# Output.net
KiCad netlist of a schematic drawn in Altium Designer
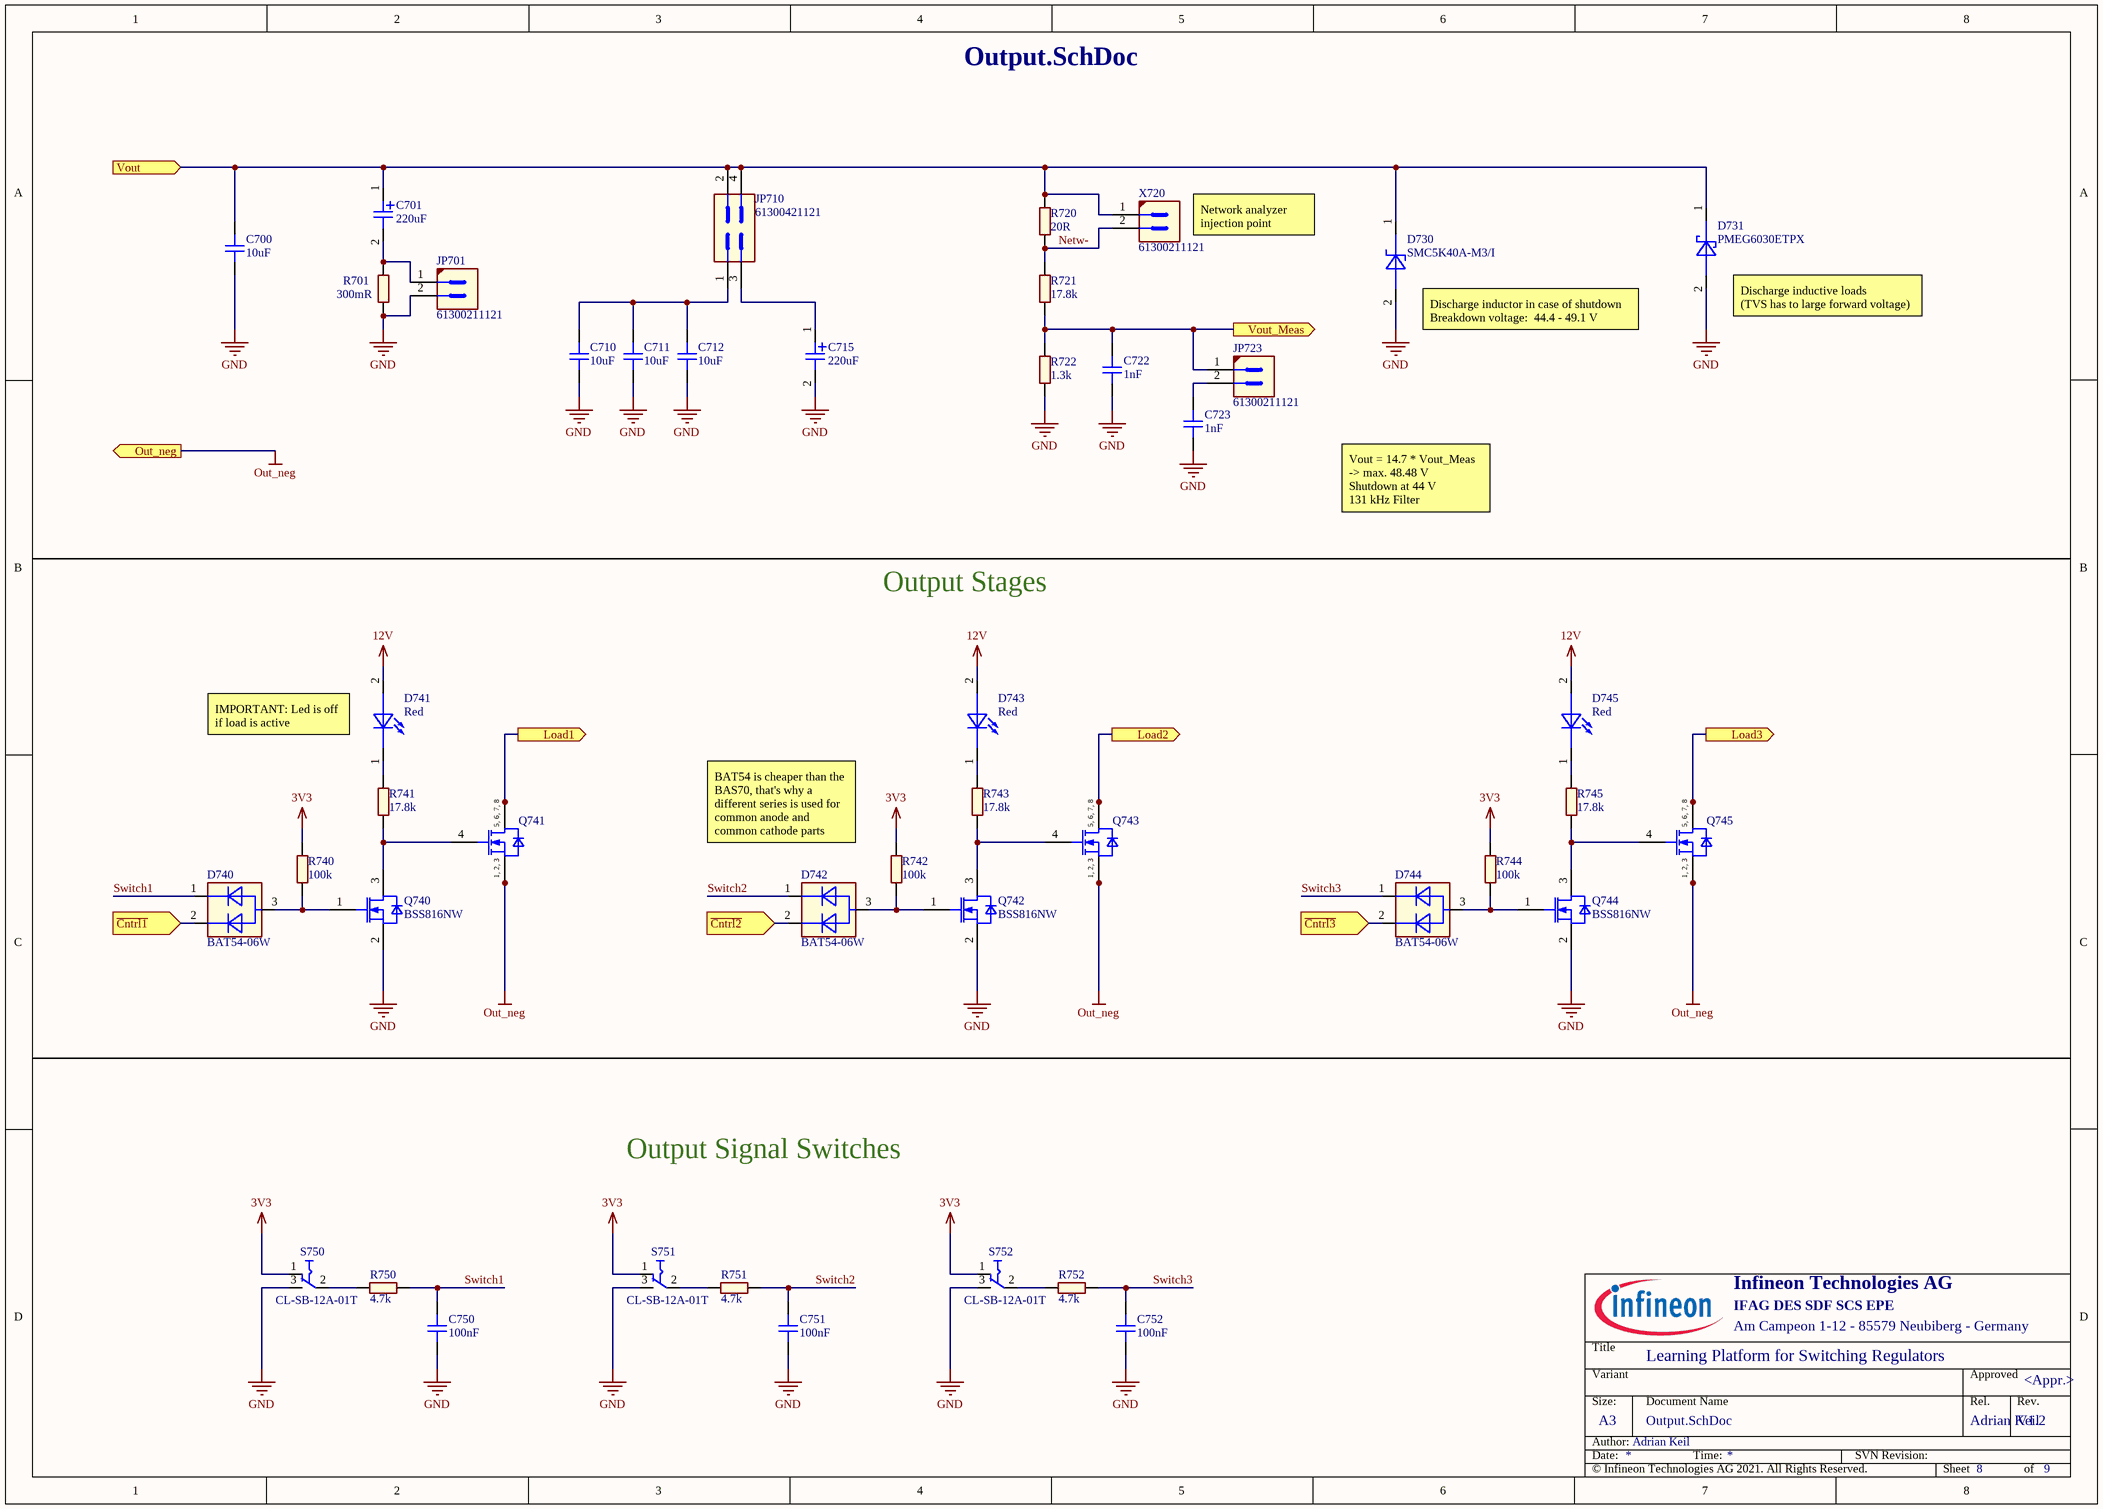
[diagram p0: Output.SchDoc]

(export (version "E")
  (design (tool "Eeschema 10.0.6"))
  (components
    (comp (ref "C700")
      (value "10uF")
      (footprint "CAPC3216X190N-1")
      (description "CAP / CERA / 10uF / 50V / 20% / X5R (EIA) / -55°C to 85°C / 1206 (3216) / SMD / -")
      (fields (field (name "MANUFACTURER") "Taiyo Yuden"))
      (libsource (lib "PCBLibraryData") (part "CAP-SGL-STD-02P_00000001"))
    )
    (comp (ref "C701")
      (value "220uF")
      (footprint "CAPAE1030X1050N-2")
      (fields (field (name "MANUFACTURER") "Wurth Elektronik"))
      (libsource (lib "PCBLibraryData") (part "CAP-SGL-POL-02P_00000002"))
    )
    (comp (ref "C710")
      (value "10uF")
      (footprint "CAPC3216X190N-1")
      (description "CAP / CERA / 10uF / 50V / 20% / X5R (EIA) / -55°C to 85°C / 1206 (3216) / SMD / -")
      (fields (field (name "MANUFACTURER") "Taiyo Yuden"))
      (libsource (lib "PCBLibraryData") (part "CAP-SGL-STD-02P_00000001"))
    )
    (comp (ref "C711")
      (value "10uF")
      (footprint "CAPC3216X190N-1")
      (description "CAP / CERA / 10uF / 50V / 20% / X5R (EIA) / -55°C to 85°C / 1206 (3216) / SMD / -")
      (fields (field (name "MANUFACTURER") "Taiyo Yuden"))
      (libsource (lib "PCBLibraryData") (part "CAP-SGL-STD-02P_00000001"))
    )
    (comp (ref "C712")
      (value "10uF")
      (footprint "CAPC3216X190N-1")
      (description "CAP / CERA / 10uF / 50V / 20% / X5R (EIA) / -55°C to 85°C / 1206 (3216) / SMD / -")
      (fields (field (name "MANUFACTURER") "Taiyo Yuden"))
      (libsource (lib "PCBLibraryData") (part "CAP-SGL-STD-02P_00000001"))
    )
    (comp (ref "C715")
      (value "220uF")
      (footprint "CAPAE1030X1050N-2")
      (fields (field (name "MANUFACTURER") "Wurth Elektronik"))
      (libsource (lib "PCBLibraryData") (part "CAP-SGL-POL-02P_00000002"))
    )
    (comp (ref "C722")
      (value "1nF")
      (footprint "CAPC1608X87N-1")
      (description "CAP / CERA / 1nF / 50V / 10% / X7R (EIA) / -55°C to 125°C / 0603 (1608) / SMD / -")
      (fields (field (name "MANUFACTURER") "Wurth Elektronik"))
      (libsource (lib "PCBLibraryData") (part "CAP-SGL-STD-02P_00000001"))
    )
    (comp (ref "C723")
      (value "1nF")
      (footprint "CAPC1608X87N-1")
      (description "CAP / CERA / 1nF / 50V / 10% / X7R (EIA) / -55°C to 125°C / 0603 (1608) / SMD / -")
      (fields (field (name "MANUFACTURER") "Wurth Elektronik"))
      (libsource (lib "PCBLibraryData") (part "CAP-SGL-STD-02P_00000001"))
    )
    (comp (ref "C750")
      (value "100nF")
      (footprint "CAPC1608X90N-2")
      (description "CAP / CERA / 100nF / 50V / 10% / X7R (EIA) / -55°C to 125°C / 0603 / SMD / -")
      (fields (field (name "MANUFACTURER") "AVX"))
      (libsource (lib "PCBLibraryData") (part "CAP-SGL-STD-02P_00000001"))
    )
    (comp (ref "C751")
      (value "100nF")
      (footprint "CAPC1608X90N-2")
      (description "CAP / CERA / 100nF / 50V / 10% / X7R (EIA) / -55°C to 125°C / 0603 / SMD / -")
      (fields (field (name "MANUFACTURER") "AVX"))
      (libsource (lib "PCBLibraryData") (part "CAP-SGL-STD-02P_00000001"))
    )
    (comp (ref "C752")
      (value "100nF")
      (footprint "CAPC1608X90N-2")
      (description "CAP / CERA / 100nF / 50V / 10% / X7R (EIA) / -55°C to 125°C / 0603 / SMD / -")
      (fields (field (name "MANUFACTURER") "AVX"))
      (libsource (lib "PCBLibraryData") (part "CAP-SGL-STD-02P_00000001"))
    )
    (comp (ref "D730")
      (value "SMC5K40A-M3/I")
      (footprint "DIOM7959X262N")
      (description "Surface Mount Transient Voltage Suppressors, Unidirectional, Very Fast Response Time")
      (fields (field (name "MANUFACTURER") "Vishay"))
      (libsource (lib "PCBLibraryData") (part "d_tvs_a"))
    )
    (comp (ref "D731")
      (value "PMEG6030ETPX")
      (footprint "SODFL4725X110N")
      (description "DIODE SCHOTTKY 60V 3A SOD128")
      (fields (field (name "MANUFACTURER") "Nexperia"))
      (libsource (lib "PCBLibraryData") (part "d_schottky_a"))
    )
    (comp (ref "D740")
      (value "BAT54-06W")
      (footprint "SOT65P210X100-3N-1-V")
      (description "Silicon Schottky Diodes")
      (fields (field (name "MANUFACTURER") "Infineon Technologies"))
      (libsource (lib "PCBLibraryData") (part "d_dual_c1c2a3_3p"))
    )
    (comp (ref "D741")
      (value "Red")
      (footprint "LEDSC160X80X80-2N-1")
      (description "WL-SMCW SMT Mono-color Chip LED Waterclear, Red,630nm")
      (fields (field (name "MANUFACTURER") "Wurth Elektronik"))
      (libsource (lib "PCBLibraryData") (part "d_led_a"))
    )
    (comp (ref "D742")
      (value "BAT54-06W")
      (footprint "SOT65P210X100-3N-1-V")
      (description "Silicon Schottky Diodes")
      (fields (field (name "MANUFACTURER") "Infineon Technologies"))
      (libsource (lib "PCBLibraryData") (part "d_dual_c1c2a3_3p"))
    )
    (comp (ref "D743")
      (value "Red")
      (footprint "LEDSC160X80X80-2N-1")
      (description "WL-SMCW SMT Mono-color Chip LED Waterclear, Red,630nm")
      (fields (field (name "MANUFACTURER") "Wurth Elektronik"))
      (libsource (lib "PCBLibraryData") (part "d_led_a"))
    )
    (comp (ref "D744")
      (value "BAT54-06W")
      (footprint "SOT65P210X100-3N-1-V")
      (description "Silicon Schottky Diodes")
      (fields (field (name "MANUFACTURER") "Infineon Technologies"))
      (libsource (lib "PCBLibraryData") (part "d_dual_c1c2a3_3p"))
    )
    (comp (ref "D745")
      (value "Red")
      (footprint "LEDSC160X80X80-2N-1")
      (description "WL-SMCW SMT Mono-color Chip LED Waterclear, Red,630nm")
      (fields (field (name "MANUFACTURER") "Wurth Elektronik"))
      (libsource (lib "PCBLibraryData") (part "d_led_a"))
    )
    (comp (ref "JP701")
      (value "61300211121")
      (footprint "CON-M-THT-61300211121")
      (description "Header, 2.54mm Pitch, 2 pin, Vertical, Single Row")
      (fields
        (field (name "LEGACY PARTNUMBER") "CON01500943")
        (field (name "MANUFACTURER") "Wurth Elektronik")
      )
      (libsource (lib "PCBLibraryData") (part "Header 2"))
    )
    (comp (ref "JP710")
      (value "61300421121")
      (footprint "CON-M-THT-61300421121")
      (description "Header, 4pins, 2.54mm pitch, Board to Board")
      (fields (field (name "MANUFACTURER") "Wurth Elektronik"))
      (libsource (lib "PCBLibraryData") (part "Header 2X2"))
    )
    (comp (ref "JP723")
      (value "61300211121")
      (footprint "CON-M-THT-61300211121")
      (description "Header, 2.54mm Pitch, 2 pin, Vertical, Single Row")
      (fields
        (field (name "LEGACY PARTNUMBER") "CON01500943")
        (field (name "MANUFACTURER") "Wurth Elektronik")
      )
      (libsource (lib "PCBLibraryData") (part "Header 2"))
    )
    (comp (ref "Q740")
      (value "BSS816NW")
      (footprint "SOT65P210X100-3N-1-V")
      (description "OptiMOS 2 Small-Signal-Transistor")
      (fields (field (name "MANUFACTURER") "Infineon Technologies"))
      (libsource (lib "PCBLibraryData") (part "igfet_n_ch_dep_dio_1g2s3d_3p"))
    )
    (comp (ref "Q741")
      (value "igfet_n_ch_enh_dio_1s2s3s4g5d6d7d8d_8p")
      (footprint "INF-PG-TSDSON-8-FL")
      (description "OptiMOS Power - MOSFET, 60 V")
      (fields
        (field (name "LEGACY PARTNUMBER") "IFX01400359")
        (field (name "MANUFACTURER") "Infineon Technologies")
      )
      (libsource (lib "PCBLibraryData") (part "igfet_n_ch_enh_dio_1s2s3s4g5d6d7d8d_8p"))
    )
    (comp (ref "Q742")
      (value "BSS816NW")
      (footprint "SOT65P210X100-3N-1-V")
      (description "OptiMOS 2 Small-Signal-Transistor")
      (fields (field (name "MANUFACTURER") "Infineon Technologies"))
      (libsource (lib "PCBLibraryData") (part "igfet_n_ch_dep_dio_1g2s3d_3p"))
    )
    (comp (ref "Q743")
      (value "igfet_n_ch_enh_dio_1s2s3s4g5d6d7d8d_8p")
      (footprint "INF-PG-TSDSON-8-FL")
      (description "OptiMOS Power - MOSFET, 60 V")
      (fields
        (field (name "LEGACY PARTNUMBER") "IFX01400359")
        (field (name "MANUFACTURER") "Infineon Technologies")
      )
      (libsource (lib "PCBLibraryData") (part "igfet_n_ch_enh_dio_1s2s3s4g5d6d7d8d_8p"))
    )
    (comp (ref "Q744")
      (value "BSS816NW")
      (footprint "SOT65P210X100-3N-1-V")
      (description "OptiMOS 2 Small-Signal-Transistor")
      (fields (field (name "MANUFACTURER") "Infineon Technologies"))
      (libsource (lib "PCBLibraryData") (part "igfet_n_ch_dep_dio_1g2s3d_3p"))
    )
    (comp (ref "Q745")
      (value "igfet_n_ch_enh_dio_1s2s3s4g5d6d7d8d_8p")
      (footprint "INF-PG-TSDSON-8-FL")
      (description "OptiMOS Power - MOSFET, 60 V")
      (fields
        (field (name "LEGACY PARTNUMBER") "IFX01400359")
        (field (name "MANUFACTURER") "Infineon Technologies")
      )
      (libsource (lib "PCBLibraryData") (part "igfet_n_ch_enh_dio_1s2s3s4g5d6d7d8d_8p"))
    )
    (comp (ref "R701")
      (value "300mR")
      (footprint "RESC6432X89N-1")
      (description "RES / STD / 300mR / 1W / 1% / 75ppm/K / -65°C to 170°C / 2512 / SMD / -")
      (fields (field (name "MANUFACTURER") "Vishay"))
      (libsource (lib "PCBLibraryData") (part "RES-SGL-STD-02P_00000006"))
    )
    (comp (ref "R720")
      (value "20R")
      (footprint "RESC1609X50N")
      (description "RES / STD / 20R / 100mW / 1% / 100ppm/K / -55°C to 155°C / 0603 / SMD / -")
      (fields (field (name "LEGACY PARTNUMBER") "RES01800947") (field (name "MANUFACTURER") "Vishay"))
      (libsource (lib "") (part "RES-SGL-STD-02P_00000006_2"))
    )
    (comp (ref "R721")
      (value "17.8k")
      (footprint "RESC1609X50N")
      (description "RES / STD / 17.8k / 100mW / 1% / 100ppm/K / -55°C to 155°C / 0603 / SMD / -")
      (fields (field (name "LEGACY PARTNUMBER") "RES01801283") (field (name "MANUFACTURER") "Vishay"))
      (libsource (lib "") (part "RES-SGL-STD-02P_00000006_1"))
    )
    (comp (ref "R722")
      (value "1.3k")
      (footprint "RESC1609X50N")
      (description "RES / STD / 1.3k / 100mW / 1% / 100ppm/K / -55°C to 155°C / 0603 / SMD / -")
      (fields (field (name "LEGACY PARTNUMBER") "RES01801155") (field (name "MANUFACTURER") "Vishay"))
      (libsource (lib "") (part "RES-SGL-STD-02P_00000006_2"))
    )
    (comp (ref "R740")
      (value "100k")
      (footprint "RESC1609X50N")
      (description "RES / STD / 100k / 100mW / 1% / 100ppm/K / -55°C to 155°C / 0603 / SMD / -")
      (fields (field (name "LEGACY PARTNUMBER") "RES01801371") (field (name "MANUFACTURER") "Vishay"))
      (libsource (lib "") (part "RES-SGL-STD-02P_00000006_2"))
    )
    (comp (ref "R741")
      (value "17.8k")
      (footprint "RESC1609X50N")
      (description "RES / STD / 17.8k / 100mW / 1% / 100ppm/K / -55°C to 155°C / 0603 / SMD / -")
      (fields (field (name "LEGACY PARTNUMBER") "RES01801283") (field (name "MANUFACTURER") "Vishay"))
      (libsource (lib "") (part "RES-SGL-STD-02P_00000006_2"))
    )
    (comp (ref "R742")
      (value "100k")
      (footprint "RESC1609X50N")
      (description "RES / STD / 100k / 100mW / 1% / 100ppm/K / -55°C to 155°C / 0603 / SMD / -")
      (fields (field (name "LEGACY PARTNUMBER") "RES01801371") (field (name "MANUFACTURER") "Vishay"))
      (libsource (lib "") (part "RES-SGL-STD-02P_00000006_2"))
    )
    (comp (ref "R743")
      (value "17.8k")
      (footprint "RESC1609X50N")
      (description "RES / STD / 17.8k / 100mW / 1% / 100ppm/K / -55°C to 155°C / 0603 / SMD / -")
      (fields (field (name "LEGACY PARTNUMBER") "RES01801283") (field (name "MANUFACTURER") "Vishay"))
      (libsource (lib "") (part "RES-SGL-STD-02P_00000006_2"))
    )
    (comp (ref "R744")
      (value "100k")
      (footprint "RESC1609X50N")
      (description "RES / STD / 100k / 100mW / 1% / 100ppm/K / -55°C to 155°C / 0603 / SMD / -")
      (fields (field (name "LEGACY PARTNUMBER") "RES01801371") (field (name "MANUFACTURER") "Vishay"))
      (libsource (lib "") (part "RES-SGL-STD-02P_00000006_2"))
    )
    (comp (ref "R745")
      (value "17.8k")
      (footprint "RESC1609X50N")
      (description "RES / STD / 17.8k / 100mW / 1% / 100ppm/K / -55°C to 155°C / 0603 / SMD / -")
      (fields (field (name "LEGACY PARTNUMBER") "RES01801283") (field (name "MANUFACTURER") "Vishay"))
      (libsource (lib "") (part "RES-SGL-STD-02P_00000006_2"))
    )
    (comp (ref "R750")
      (value "4.7k")
      (footprint "RESC1609X50N")
      (description "RES / STD / 4.7k / 100mW / 1% / 100ppm/K / -55°C to 155°C / 0603 / SMD / -")
      (fields (field (name "LEGACY PARTNUMBER") "RES01801219") (field (name "MANUFACTURER") "Vishay"))
      (libsource (lib "PCBLibraryData") (part "RES-SGL-STD-02P_00000006"))
    )
    (comp (ref "R751")
      (value "4.7k")
      (footprint "RESC1609X50N")
      (description "RES / STD / 4.7k / 100mW / 1% / 100ppm/K / -55°C to 155°C / 0603 / SMD / -")
      (fields (field (name "LEGACY PARTNUMBER") "RES01801219") (field (name "MANUFACTURER") "Vishay"))
      (libsource (lib "PCBLibraryData") (part "RES-SGL-STD-02P_00000006"))
    )
    (comp (ref "R752")
      (value "4.7k")
      (footprint "RESC1609X50N")
      (description "RES / STD / 4.7k / 100mW / 1% / 100ppm/K / -55°C to 155°C / 0603 / SMD / -")
      (fields (field (name "LEGACY PARTNUMBER") "RES01801219") (field (name "MANUFACTURER") "Vishay"))
      (libsource (lib "PCBLibraryData") (part "RES-SGL-STD-02P_00000006"))
    )
    (comp (ref "S750")
      (value "CL-SB-12A-01T")
      (footprint "SW-SMD-CL-SB-12A-01T")
      (description "Slid Switch, 12V, 200mA")
      (fields (field (name "MANUFACTURER") "NIDEC COPAL ELECTRONICS, Inc."))
      (libsource (lib "PCBLibraryData") (part "sw_co213_3p"))
    )
    (comp (ref "S751")
      (value "CL-SB-12A-01T")
      (footprint "SW-SMD-CL-SB-12A-01T")
      (description "Slid Switch, 12V, 200mA")
      (fields (field (name "MANUFACTURER") "NIDEC COPAL ELECTRONICS, Inc."))
      (libsource (lib "PCBLibraryData") (part "sw_co213_3p"))
    )
    (comp (ref "S752")
      (value "CL-SB-12A-01T")
      (footprint "SW-SMD-CL-SB-12A-01T")
      (description "Slid Switch, 12V, 200mA")
      (fields (field (name "MANUFACTURER") "NIDEC COPAL ELECTRONICS, Inc."))
      (libsource (lib "PCBLibraryData") (part "sw_co213_3p"))
    )
    (comp (ref "X720")
      (value "61300211121")
      (footprint "CON-M-THT-61300211121")
      (description "Header, 2.54mm Pitch, 2 pin, Vertical, Single Row")
      (fields
        (field (name "LEGACY PARTNUMBER") "CON01500943")
        (field (name "MANUFACTURER") "Wurth Elektronik")
      )
      (libsource (lib "PCBLibraryData") (part "Header 2"))
    )
  )
  (nets
    (net (code "1") (name "/Cntrl1") (class "Default")
      (node (ref "D740") (pin "2") (pinfunction "CATHODE2_2") (pintype "passive"))
    )
    (net (code "2") (name "/Cntrl2") (class "Default")
      (node (ref "D742") (pin "2") (pinfunction "CATHODE2_2") (pintype "passive"))
    )
    (net (code "3") (name "/Cntrl3") (class "Default")
      (node (ref "D744") (pin "2") (pinfunction "CATHODE2_2") (pintype "passive"))
    )
    (net (code "4") (name "/Load1") (class "Default")
      (node (ref "Q741") (pin "5") (pinfunction "DRAIN_5") (pintype "passive"))
      (node (ref "Q741") (pin "6") (pinfunction "DRAIN_6") (pintype "passive"))
      (node (ref "Q741") (pin "7") (pinfunction "DRAIN_7") (pintype "passive"))
      (node (ref "Q741") (pin "8") (pinfunction "DRAIN_8") (pintype "passive"))
    )
    (net (code "5") (name "/Load2") (class "Default")
      (node (ref "Q743") (pin "5") (pinfunction "DRAIN_5") (pintype "passive"))
      (node (ref "Q743") (pin "6") (pinfunction "DRAIN_6") (pintype "passive"))
      (node (ref "Q743") (pin "7") (pinfunction "DRAIN_7") (pintype "passive"))
      (node (ref "Q743") (pin "8") (pinfunction "DRAIN_8") (pintype "passive"))
    )
    (net (code "6") (name "/Load3") (class "Default")
      (node (ref "Q745") (pin "5") (pinfunction "DRAIN_5") (pintype "passive"))
      (node (ref "Q745") (pin "6") (pinfunction "DRAIN_6") (pintype "passive"))
      (node (ref "Q745") (pin "7") (pinfunction "DRAIN_7") (pintype "passive"))
      (node (ref "Q745") (pin "8") (pinfunction "DRAIN_8") (pintype "passive"))
    )
    (net (code "7") (name "/Netw-") (class "Default")
      (node (ref "R720") (pin "1") (pinfunction "1_1") (pintype "passive"))
      (node (ref "R721") (pin "1") (pinfunction "1_1") (pintype "passive"))
      (node (ref "X720") (pin "2") (pinfunction "2_2") (pintype "passive"))
    )
    (net (code "8") (name "/Switch1") (class "Default")
      (node (ref "C750") (pin "2") (pinfunction "2_2") (pintype "passive"))
      (node (ref "D740") (pin "1") (pinfunction "CATHODE1_1") (pintype "passive"))
      (node (ref "R750") (pin "2") (pinfunction "2_2") (pintype "passive"))
    )
    (net (code "9") (name "/Switch2") (class "Default")
      (node (ref "C751") (pin "2") (pinfunction "2_2") (pintype "passive"))
      (node (ref "D742") (pin "1") (pinfunction "CATHODE1_1") (pintype "passive"))
      (node (ref "R751") (pin "2") (pinfunction "2_2") (pintype "passive"))
    )
    (net (code "10") (name "/Switch3") (class "Default")
      (node (ref "C752") (pin "2") (pinfunction "2_2") (pintype "passive"))
      (node (ref "D744") (pin "1") (pinfunction "CATHODE1_1") (pintype "passive"))
      (node (ref "R752") (pin "2") (pinfunction "2_2") (pintype "passive"))
    )
    (net (code "11") (name "/Vout") (class "Default")
      (node (ref "C700") (pin "2") (pinfunction "2_2") (pintype "passive"))
      (node (ref "C701") (pin "1") (pinfunction "1_1") (pintype "passive"))
      (node (ref "D730") (pin "1") (pinfunction "CATHODE_1") (pintype "passive"))
      (node (ref "D731") (pin "1") (pinfunction "Cathode_1") (pintype "passive"))
      (node (ref "JP710") (pin "2") (pinfunction "2_2") (pintype "passive"))
      (node (ref "JP710") (pin "4") (pinfunction "4_4") (pintype "passive"))
      (node (ref "R720") (pin "2") (pinfunction "2_2") (pintype "passive"))
      (node (ref "X720") (pin "1") (pinfunction "1_1") (pintype "passive"))
    )
    (net (code "12") (name "/Vout_Meas") (class "Default")
      (node (ref "C722") (pin "2") (pinfunction "2_2") (pintype "passive"))
      (node (ref "JP723") (pin "1") (pinfunction "1_1") (pintype "passive"))
      (node (ref "R721") (pin "2") (pinfunction "2_2") (pintype "passive"))
      (node (ref "R722") (pin "2") (pinfunction "2_2") (pintype "passive"))
    )
    (net (code "13") (name "3V3") (class "Default")
      (node (ref "R740") (pin "2") (pinfunction "2_2") (pintype "passive"))
      (node (ref "R742") (pin "2") (pinfunction "2_2") (pintype "passive"))
      (node (ref "R744") (pin "2") (pinfunction "2_2") (pintype "passive"))
      (node (ref "S750") (pin "1") (pinfunction "1_1") (pintype "passive"))
      (node (ref "S751") (pin "1") (pinfunction "1_1") (pintype "passive"))
      (node (ref "S752") (pin "1") (pinfunction "1_1") (pintype "passive"))
    )
    (net (code "14") (name "12V") (class "Default")
      (node (ref "D741") (pin "2") (pinfunction "Anode_2") (pintype "passive"))
      (node (ref "D743") (pin "2") (pinfunction "Anode_2") (pintype "passive"))
      (node (ref "D745") (pin "2") (pinfunction "Anode_2") (pintype "passive"))
    )
    (net (code "15") (name "GND") (class "Default")
      (node (ref "C700") (pin "1") (pinfunction "1_1") (pintype "passive"))
      (node (ref "C710") (pin "1") (pinfunction "1_1") (pintype "passive"))
      (node (ref "C711") (pin "1") (pinfunction "1_1") (pintype "passive"))
      (node (ref "C712") (pin "1") (pinfunction "1_1") (pintype "passive"))
      (node (ref "C715") (pin "2") (pinfunction "2_2") (pintype "passive"))
      (node (ref "C722") (pin "1") (pinfunction "1_1") (pintype "passive"))
      (node (ref "C723") (pin "1") (pinfunction "1_1") (pintype "passive"))
      (node (ref "C750") (pin "1") (pinfunction "1_1") (pintype "passive"))
      (node (ref "C751") (pin "1") (pinfunction "1_1") (pintype "passive"))
      (node (ref "C752") (pin "1") (pinfunction "1_1") (pintype "passive"))
      (node (ref "D730") (pin "2") (pinfunction "ANODE_2") (pintype "passive"))
      (node (ref "D731") (pin "2") (pinfunction "Anode_2") (pintype "passive"))
      (node (ref "JP701") (pin "2") (pinfunction "2_2") (pintype "passive"))
      (node (ref "Q740") (pin "2") (pinfunction "SOURCE_2") (pintype "passive"))
      (node (ref "Q742") (pin "2") (pinfunction "SOURCE_2") (pintype "passive"))
      (node (ref "Q744") (pin "2") (pinfunction "SOURCE_2") (pintype "passive"))
      (node (ref "R701") (pin "1") (pinfunction "1_1") (pintype "passive"))
      (node (ref "R722") (pin "1") (pinfunction "1_1") (pintype "passive"))
      (node (ref "S750") (pin "3") (pinfunction "3_3") (pintype "passive"))
      (node (ref "S751") (pin "3") (pinfunction "3_3") (pintype "passive"))
      (node (ref "S752") (pin "3") (pinfunction "3_3") (pintype "passive"))
    )
    (net (code "16") (name "Net-(C701-Pad2)") (class "Default")
      (node (ref "C701") (pin "2") (pinfunction "2_2") (pintype "passive"))
      (node (ref "JP701") (pin "1") (pinfunction "1_1") (pintype "passive"))
      (node (ref "R701") (pin "2") (pinfunction "2_2") (pintype "passive"))
    )
    (net (code "17") (name "Net-(C710-Pad2)") (class "Default")
      (node (ref "C710") (pin "2") (pinfunction "2_2") (pintype "passive"))
      (node (ref "C711") (pin "2") (pinfunction "2_2") (pintype "passive"))
      (node (ref "C712") (pin "2") (pinfunction "2_2") (pintype "passive"))
      (node (ref "JP710") (pin "1") (pinfunction "1_1") (pintype "passive"))
    )
    (net (code "18") (name "Net-(C715-Pad1)") (class "Default")
      (node (ref "C715") (pin "1") (pinfunction "1_1") (pintype "passive"))
      (node (ref "JP710") (pin "3") (pinfunction "3_3") (pintype "passive"))
    )
    (net (code "19") (name "Net-(C723-Pad2)") (class "Default")
      (node (ref "C723") (pin "2") (pinfunction "2_2") (pintype "passive"))
      (node (ref "JP723") (pin "2") (pinfunction "2_2") (pintype "passive"))
    )
    (net (code "20") (name "Net-(D740-ANODE)") (class "Default")
      (node (ref "D740") (pin "3") (pinfunction "ANODE_3") (pintype "passive"))
      (node (ref "Q740") (pin "1") (pinfunction "GATE_1") (pintype "passive"))
      (node (ref "R740") (pin "1") (pinfunction "1_1") (pintype "passive"))
    )
    (net (code "21") (name "Net-(D741-Cathode)") (class "Default")
      (node (ref "D741") (pin "1") (pinfunction "Cathode_1") (pintype "passive"))
      (node (ref "R741") (pin "2") (pinfunction "2_2") (pintype "passive"))
    )
    (net (code "22") (name "Net-(D742-ANODE)") (class "Default")
      (node (ref "D742") (pin "3") (pinfunction "ANODE_3") (pintype "passive"))
      (node (ref "Q742") (pin "1") (pinfunction "GATE_1") (pintype "passive"))
      (node (ref "R742") (pin "1") (pinfunction "1_1") (pintype "passive"))
    )
    (net (code "23") (name "Net-(D743-Cathode)") (class "Default")
      (node (ref "D743") (pin "1") (pinfunction "Cathode_1") (pintype "passive"))
      (node (ref "R743") (pin "2") (pinfunction "2_2") (pintype "passive"))
    )
    (net (code "24") (name "Net-(D744-ANODE)") (class "Default")
      (node (ref "D744") (pin "3") (pinfunction "ANODE_3") (pintype "passive"))
      (node (ref "Q744") (pin "1") (pinfunction "GATE_1") (pintype "passive"))
      (node (ref "R744") (pin "1") (pinfunction "1_1") (pintype "passive"))
    )
    (net (code "25") (name "Net-(D745-Cathode)") (class "Default")
      (node (ref "D745") (pin "1") (pinfunction "Cathode_1") (pintype "passive"))
      (node (ref "R745") (pin "2") (pinfunction "2_2") (pintype "passive"))
    )
    (net (code "26") (name "Net-(Q740-DRAIN)") (class "Default")
      (node (ref "Q740") (pin "3") (pinfunction "DRAIN_3") (pintype "passive"))
      (node (ref "Q741") (pin "4") (pinfunction "GATE_4") (pintype "passive"))
      (node (ref "R741") (pin "1") (pinfunction "1_1") (pintype "passive"))
    )
    (net (code "27") (name "Net-(Q742-DRAIN)") (class "Default")
      (node (ref "Q742") (pin "3") (pinfunction "DRAIN_3") (pintype "passive"))
      (node (ref "Q743") (pin "4") (pinfunction "GATE_4") (pintype "passive"))
      (node (ref "R743") (pin "1") (pinfunction "1_1") (pintype "passive"))
    )
    (net (code "28") (name "Net-(Q744-DRAIN)") (class "Default")
      (node (ref "Q744") (pin "3") (pinfunction "DRAIN_3") (pintype "passive"))
      (node (ref "Q745") (pin "4") (pinfunction "GATE_4") (pintype "passive"))
      (node (ref "R745") (pin "1") (pinfunction "1_1") (pintype "passive"))
    )
    (net (code "29") (name "Net-(R750-Pad1)") (class "Default")
      (node (ref "R750") (pin "1") (pinfunction "1_1") (pintype "passive"))
      (node (ref "S750") (pin "2") (pinfunction "2_2") (pintype "passive"))
    )
    (net (code "30") (name "Net-(R751-Pad1)") (class "Default")
      (node (ref "R751") (pin "1") (pinfunction "1_1") (pintype "passive"))
      (node (ref "S751") (pin "2") (pinfunction "2_2") (pintype "passive"))
    )
    (net (code "31") (name "Net-(R752-Pad1)") (class "Default")
      (node (ref "R752") (pin "1") (pinfunction "1_1") (pintype "passive"))
      (node (ref "S752") (pin "2") (pinfunction "2_2") (pintype "passive"))
    )
    (net (code "32") (name "Out_neg") (class "Default")
      (node (ref "Q741") (pin "1") (pinfunction "SOURCE_1") (pintype "passive"))
      (node (ref "Q741") (pin "2") (pinfunction "SOURCE_2") (pintype "passive"))
      (node (ref "Q741") (pin "3") (pinfunction "SOURCE_3") (pintype "passive"))
      (node (ref "Q743") (pin "1") (pinfunction "SOURCE_1") (pintype "passive"))
      (node (ref "Q743") (pin "2") (pinfunction "SOURCE_2") (pintype "passive"))
      (node (ref "Q743") (pin "3") (pinfunction "SOURCE_3") (pintype "passive"))
      (node (ref "Q745") (pin "1") (pinfunction "SOURCE_1") (pintype "passive"))
      (node (ref "Q745") (pin "2") (pinfunction "SOURCE_2") (pintype "passive"))
      (node (ref "Q745") (pin "3") (pinfunction "SOURCE_3") (pintype "passive"))
    )
  )
)
